# TIA2_1ch.net
KiCad netlist of a schematic drawn in EAGLE
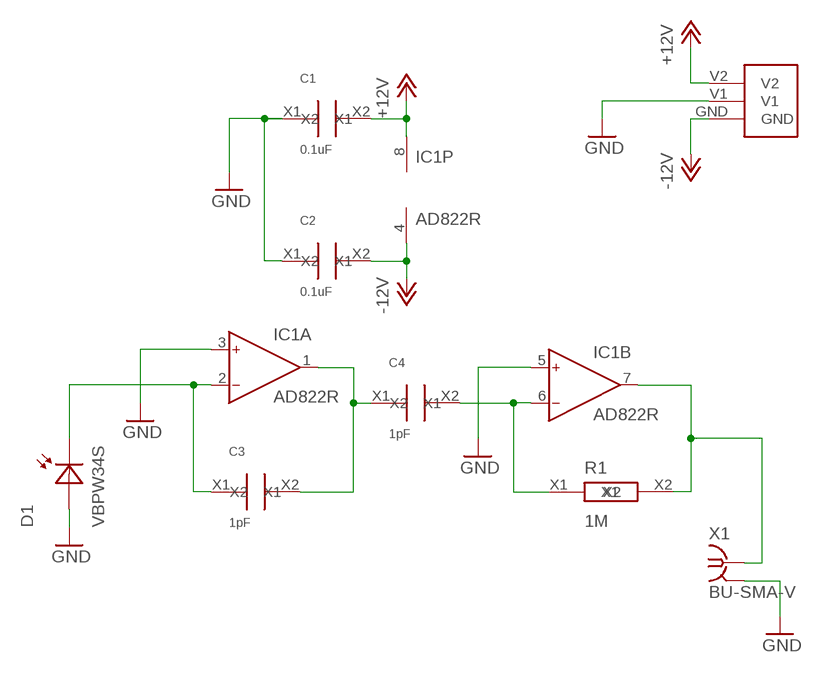
[diagram p0: schematic, sheet 1]

(export (version "E")
  (design (tool "Eeschema 10.0.6"))
  (components
    (comp (ref "C1")
      (value "0.1uF")
      (footprint "eagle-import:SMD_2.1X1.25")
      (libsource (lib "eagle-import") (part "C_SMD_2.1X1.25"))
    )
    (comp (ref "C2")
      (value "0.1uF")
      (footprint "eagle-import:SMD_2.1X1.25")
      (libsource (lib "eagle-import") (part "C_SMD_2.1X1.25"))
    )
    (comp (ref "C3")
      (value "1pF")
      (footprint "eagle-import:SMD_2.1X1.25")
      (libsource (lib "eagle-import") (part "C_SMD_2.1X1.25"))
    )
    (comp (ref "C4")
      (value "1pF")
      (footprint "eagle-import:SMD_2.1X1.25")
      (libsource (lib "eagle-import") (part "C_SMD_2.1X1.25"))
    )
    (comp (ref "D1")
      (value "VBPW34S")
      (footprint "eagle-import:SOD6439X130N")
      (fields (field (name "DIGI-KEY_PART_NUMBER") "751-1500-1-ND") (field (name "MF") "Vishay"))
      (libsource (lib "eagle-import") (part "VBPW34S"))
    )
    (comp (ref "IC1")
      (value "AD822R")
      (footprint "eagle-import:SO8")
      (fields (field (name "MF") "ANALOG DEVICES") (field (name "MPN") "AD822BRZ"))
      (libsource (lib "eagle-import") (part "AD822R"))
    )
    (comp (ref "R1")
      (value "1M")
      (footprint "eagle-import:SMD_2.1X1.25")
      (libsource (lib "eagle-import") (part "R_SMD_2.1X1.25"))
    )
    (comp (ref "U$1")
      (value "BAT3_PLUG")
      (footprint "eagle-import:BAT3_PLUG")
      (libsource (lib "eagle-import") (part "BAT3_PLUG"))
    )
    (comp (ref "X1")
      (value "BU-SMA-V")
      (footprint "eagle-import:BU-SMA-V")
      (libsource (lib "eagle-import") (part "BU-SMA-V"))
    )
  )
  (nets
    (net (code "1") (name "+12V") (class "Default")
      (node (ref "C1") (pin "X2") (pinfunction "X2_X2") (pintype "bidirectional"))
      (node (ref "IC1") (pin "8") (pinfunction "V+_8") (pintype "power_in"))
      (node (ref "U$1") (pin "V2") (pinfunction "V2_V2") (pintype "bidirectional"))
    )
    (net (code "2") (name "-12V") (class "Default")
      (node (ref "C2") (pin "X2") (pinfunction "X2_X2") (pintype "bidirectional"))
      (node (ref "IC1") (pin "4") (pinfunction "V-_4") (pintype "power_in"))
      (node (ref "U$1") (pin "GND") (pinfunction "GND_GND") (pintype "bidirectional"))
    )
    (net (code "3") (name "GND") (class "Default")
      (node (ref "C1") (pin "X1") (pinfunction "X1_X1") (pintype "bidirectional"))
      (node (ref "C2") (pin "X1") (pinfunction "X1_X1") (pintype "bidirectional"))
      (node (ref "D1") (pin "A") (pinfunction "A_A") (pintype "passive"))
      (node (ref "IC1") (pin "3") (pinfunction "IN+_3") (pintype "input"))
      (node (ref "IC1") (pin "5") (pinfunction "IN+_5") (pintype "input"))
      (node (ref "U$1") (pin "V1") (pinfunction "V1_V1") (pintype "bidirectional"))
      (node (ref "X1") (pin "2") (pinfunction "2_2") (pintype "passive"))
      (node (ref "X1") (pin "3") (pinfunction "2_3") (pintype "passive"))
      (node (ref "X1") (pin "4") (pinfunction "2_4") (pintype "passive"))
      (node (ref "X1") (pin "5") (pinfunction "2_5") (pintype "passive"))
    )
    (net (code "4") (name "Net-(IC1A-IN-)") (class "Default")
      (node (ref "C3") (pin "X1") (pinfunction "X1_X1") (pintype "bidirectional"))
      (node (ref "D1") (pin "C") (pinfunction "C_C") (pintype "passive"))
      (node (ref "IC1") (pin "2") (pinfunction "IN-_2") (pintype "input"))
    )
    (net (code "5") (name "Net-(IC1A-OUT)") (class "Default")
      (node (ref "C3") (pin "X2") (pinfunction "X2_X2") (pintype "bidirectional"))
      (node (ref "C4") (pin "X1") (pinfunction "X1_X1") (pintype "bidirectional"))
      (node (ref "IC1") (pin "1") (pinfunction "OUT_1") (pintype "output"))
    )
    (net (code "6") (name "Net-(IC1B-IN-)") (class "Default")
      (node (ref "C4") (pin "X2") (pinfunction "X2_X2") (pintype "bidirectional"))
      (node (ref "IC1") (pin "6") (pinfunction "IN-_6") (pintype "input"))
      (node (ref "R1") (pin "X1") (pinfunction "X1_X1") (pintype "bidirectional"))
    )
    (net (code "7") (name "Net-(IC1B-OUT)") (class "Default")
      (node (ref "IC1") (pin "7") (pinfunction "OUT_7") (pintype "output"))
      (node (ref "R1") (pin "X2") (pinfunction "X2_X2") (pintype "bidirectional"))
      (node (ref "X1") (pin "1") (pinfunction "1_1") (pintype "passive"))
    )
  )
)
